# led.net
KiCad netlist of a schematic drawn in Altium Designer
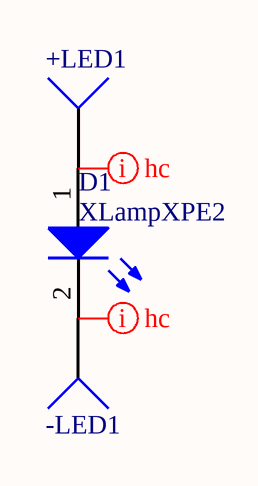
[diagram p0: led.SchDoc]

(export (version "E")
  (design (tool "Eeschema 10.0.6"))
  (components
    (comp (ref "+LED1")
      (value "+LED")
      (footprint "PIN1L")
      (description "Socket")
      (fields (field (name "PUBLISHER") "Altium Limited"))
      (libsource (lib "misc") (part "Socket"))
    )
    (comp (ref "-LED1")
      (value "-LED")
      (footprint "PIN1L")
      (description "Socket")
      (fields (field (name "PUBLISHER") "Altium Limited"))
      (libsource (lib "misc") (part "Socket"))
    )
    (comp (ref "D1")
      (value "XLampXPE2")
      (footprint "XLAMP")
      (description "Typical INFRARED GaAs LED")
      (fields (field (name "PUBLISHER") "Altium Limited"))
      (libsource (lib "Miscellaneous Devices") (part "LED0"))
    )
  )
  (nets
    (net (code "1") (name "Net-(D1-A)") (class "Default")
      (node (ref "+LED1") (pin "1") (pinfunction "1_1") (pintype "passive"))
      (node (ref "D1") (pin "1") (pinfunction "A_1") (pintype "passive"))
    )
    (net (code "2") (name "Net-(D1-K)") (class "Default")
      (node (ref "-LED1") (pin "1") (pinfunction "1_1") (pintype "passive"))
      (node (ref "D1") (pin "2") (pinfunction "K_2") (pintype "passive"))
    )
  )
)
